# display_spi.net
KiCad netlist of a schematic drawn in EAGLE
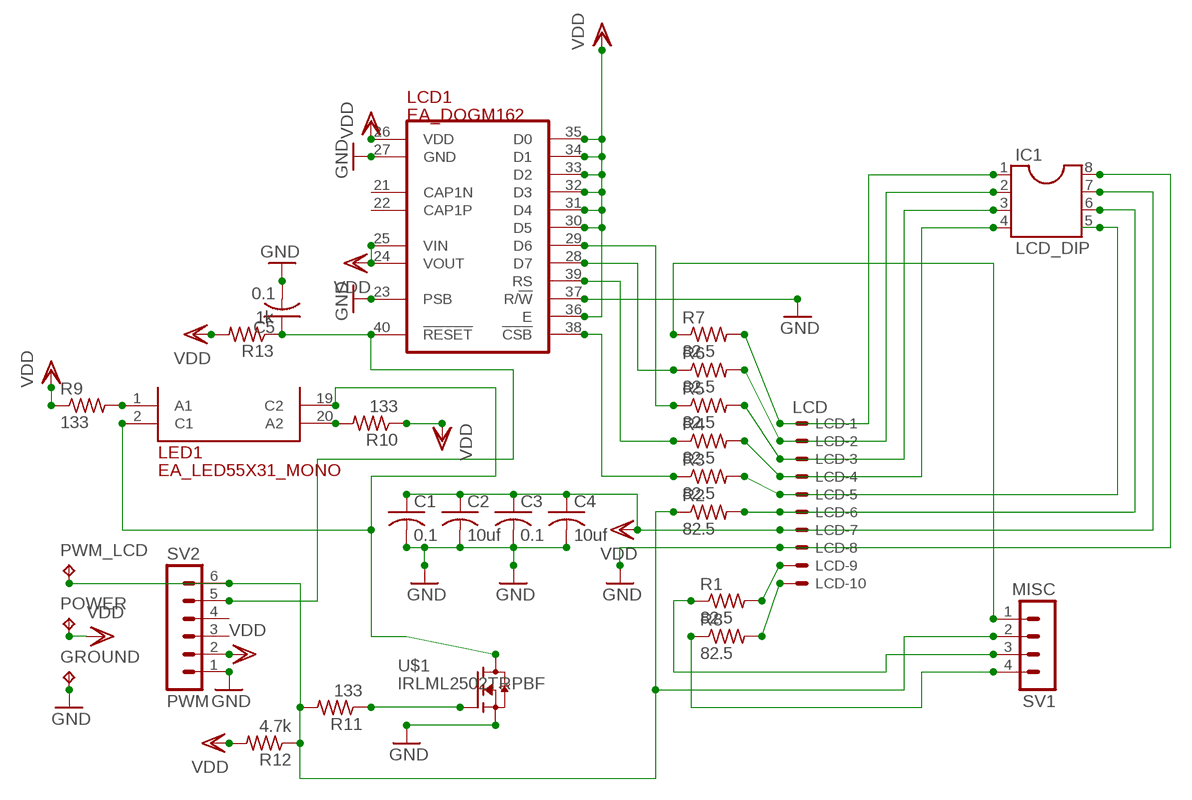
[diagram p0: schematic, sheet 1]

(export (version "E")
  (design (tool "Eeschema 10.0.6"))
  (components
    (comp (ref "C1")
      (value "0.1")
      (footprint "eagle-import:C1206")
      (libsource (lib "eagle-import") (part "C-USC1206"))
    )
    (comp (ref "C2")
      (value "10uf")
      (footprint "eagle-import:C1206")
      (libsource (lib "eagle-import") (part "C-USC1206"))
    )
    (comp (ref "C3")
      (value "0.1")
      (footprint "eagle-import:C1206")
      (libsource (lib "eagle-import") (part "C-USC1206"))
    )
    (comp (ref "C4")
      (value "10uf")
      (footprint "eagle-import:C1206")
      (libsource (lib "eagle-import") (part "C-USC1206"))
    )
    (comp (ref "C5")
      (value "0.1")
      (footprint "eagle-import:C1206")
      (libsource (lib "eagle-import") (part "C-USC1206"))
    )
    (comp (ref "GROUND")
      (value "TPB1,27")
      (footprint "eagle-import:B1,27")
      (libsource (lib "eagle-import") (part "TPB1,27"))
    )
    (comp (ref "IC1")
      (value "LCD_DIP")
      (footprint "eagle-import:SOCKET-08")
      (libsource (lib "eagle-import") (part "DIL8S"))
    )
    (comp (ref "LCD")
      (value "LCD")
      (footprint "eagle-import:22-23-2101")
      (fields (field (name "MF") "MOLEX") (field (name "MPN") "22-23-2101"))
      (libsource (lib "eagle-import") (part "22-23-2101"))
    )
    (comp (ref "LCD1")
      (value "EA_DOGM162")
      (footprint "eagle-import:EA_DOGM")
      (libsource (lib "eagle-import") (part "EA_DOGM162"))
    )
    (comp (ref "LED1")
      (value "EA_LED55X31_MONO")
      (footprint "eagle-import:EA_LED55X31")
      (libsource (lib "eagle-import") (part "EA_LED55X31_MONO"))
    )
    (comp (ref "POWER")
      (value "TPB1,27")
      (footprint "eagle-import:B1,27")
      (libsource (lib "eagle-import") (part "TPB1,27"))
    )
    (comp (ref "PWM_LCD")
      (value "PWM")
      (footprint "eagle-import:B1,27")
      (libsource (lib "eagle-import") (part "TPB1,27"))
    )
    (comp (ref "R1")
      (value "82.5")
      (footprint "eagle-import:R0805")
      (libsource (lib "eagle-import") (part "R-US_R0805"))
    )
    (comp (ref "R2")
      (value "82.5")
      (footprint "eagle-import:R0805")
      (libsource (lib "eagle-import") (part "R-US_R0805"))
    )
    (comp (ref "R3")
      (value "82.5")
      (footprint "eagle-import:R0805")
      (libsource (lib "eagle-import") (part "R-US_R0805"))
    )
    (comp (ref "R4")
      (value "82.5")
      (footprint "eagle-import:R0805")
      (libsource (lib "eagle-import") (part "R-US_R0805"))
    )
    (comp (ref "R5")
      (value "82.5")
      (footprint "eagle-import:R0805")
      (libsource (lib "eagle-import") (part "R-US_R0805"))
    )
    (comp (ref "R6")
      (value "82.5")
      (footprint "eagle-import:R0805")
      (libsource (lib "eagle-import") (part "R-US_R0805"))
    )
    (comp (ref "R7")
      (value "82.5")
      (footprint "eagle-import:R0805")
      (libsource (lib "eagle-import") (part "R-US_R0805"))
    )
    (comp (ref "R8")
      (value "82.5")
      (footprint "eagle-import:R0805")
      (libsource (lib "eagle-import") (part "R-US_R0805"))
    )
    (comp (ref "R9")
      (value "133")
      (footprint "eagle-import:R1206")
      (libsource (lib "eagle-import") (part "R-US_R1206"))
    )
    (comp (ref "R10")
      (value "133")
      (footprint "eagle-import:R1206")
      (libsource (lib "eagle-import") (part "R-US_R1206"))
    )
    (comp (ref "R11")
      (value "133")
      (footprint "eagle-import:R1206")
      (libsource (lib "eagle-import") (part "R-US_R1206"))
    )
    (comp (ref "R12")
      (value "4.7k")
      (footprint "eagle-import:R1206")
      (libsource (lib "eagle-import") (part "R-US_R1206"))
    )
    (comp (ref "R13")
      (value "1k")
      (footprint "eagle-import:R1206")
      (libsource (lib "eagle-import") (part "R-US_R1206"))
    )
    (comp (ref "SV1")
      (value "MISC")
      (footprint "eagle-import:MA04-1")
      (libsource (lib "eagle-import") (part "MA04-1"))
    )
    (comp (ref "SV2")
      (value "PWM")
      (footprint "eagle-import:MA06-1")
      (libsource (lib "eagle-import") (part "MA06-1"))
    )
    (comp (ref "U$1")
      (value "IRLML2502TRPBF")
      (footprint "eagle-import:SOT23")
      (fields (field (name "DIGI-KEY_PART_NUMBER") "IRLML2502TRPBFCT-ND") (field (name "MF") "Infineon"))
      (libsource (lib "eagle-import") (part "IRLML2502TRPBF"))
    )
  )
  (nets
    (net (code "1") (name "GND") (class "Default")
      (node (ref "C1") (pin "2") (pinfunction "2_2") (pintype "passive"))
      (node (ref "C2") (pin "2") (pinfunction "2_2") (pintype "passive"))
      (node (ref "C3") (pin "2") (pinfunction "2_2") (pintype "passive"))
      (node (ref "C4") (pin "2") (pinfunction "2_2") (pintype "passive"))
      (node (ref "C5") (pin "2") (pinfunction "2_2") (pintype "passive"))
      (node (ref "GROUND") (pin "TP") (pinfunction "TP_TP") (pintype "input"))
      (node (ref "IC1") (pin "8") (pinfunction "8_8") (pintype "passive"))
      (node (ref "LCD") (pin "8") (pinfunction "S_8") (pintype "passive"))
      (node (ref "LCD1") (pin "23") (pinfunction "PSB_23") (pintype "input"))
      (node (ref "LCD1") (pin "27") (pinfunction "GND_27") (pintype "power_in"))
      (node (ref "LCD1") (pin "37") (pinfunction "R/~{W}_37") (pintype "input"))
      (node (ref "SV2") (pin "1") (pinfunction "1_1") (pintype "passive"))
      (node (ref "U$1") (pin "2") (pinfunction "S_2") (pintype "passive"))
    )
    (net (code "2") (name "Net-(LCD1-D6)") (class "Default")
      (node (ref "LCD1") (pin "29") (pinfunction "D6_29") (pintype "bidirectional"))
      (node (ref "R5") (pin "1") (pinfunction "1_1") (pintype "passive"))
    )
    (net (code "3") (name "Net-(LCD1-D7)") (class "Default")
      (node (ref "LCD1") (pin "28") (pinfunction "D7_28") (pintype "bidirectional"))
      (node (ref "R6") (pin "1") (pinfunction "1_1") (pintype "passive"))
    )
    (net (code "4") (name "Net-(LCD1-RS)") (class "Default")
      (node (ref "LCD1") (pin "39") (pinfunction "RS_39") (pintype "input"))
      (node (ref "R4") (pin "1") (pinfunction "1_1") (pintype "passive"))
    )
    (net (code "5") (name "Net-(LCD1-~{CSB})") (class "Default")
      (node (ref "LCD1") (pin "38") (pinfunction "~{CSB}_38") (pintype "input"))
      (node (ref "R3") (pin "1") (pinfunction "1_1") (pintype "passive"))
    )
    (net (code "6") (name "Net-(LCD1-~{RESET})") (class "Default")
      (node (ref "C5") (pin "1") (pinfunction "1_1") (pintype "passive"))
      (node (ref "LCD1") (pin "40") (pinfunction "~{RESET}_40") (pintype "input"))
      (node (ref "R13") (pin "1") (pinfunction "1_1") (pintype "passive"))
      (node (ref "SV2") (pin "5") (pinfunction "5_5") (pintype "passive"))
    )
    (net (code "7") (name "Net-(LCDA-S)") (class "Default")
      (node (ref "IC1") (pin "1") (pinfunction "1_1") (pintype "passive"))
      (node (ref "LCD") (pin "1") (pinfunction "S_1") (pintype "passive"))
      (node (ref "R7") (pin "2") (pinfunction "2_2") (pintype "passive"))
    )
    (net (code "8") (name "Net-(LCDB-S)") (class "Default")
      (node (ref "LCD") (pin "10") (pinfunction "S_10") (pintype "passive"))
      (node (ref "R8") (pin "2") (pinfunction "2_2") (pintype "passive"))
    )
    (net (code "9") (name "Net-(LCDC-S)") (class "Default")
      (node (ref "IC1") (pin "2") (pinfunction "2_2") (pintype "passive"))
      (node (ref "LCD") (pin "2") (pinfunction "S_2") (pintype "passive"))
      (node (ref "R6") (pin "2") (pinfunction "2_2") (pintype "passive"))
    )
    (net (code "10") (name "Net-(LCDD-S)") (class "Default")
      (node (ref "IC1") (pin "3") (pinfunction "3_3") (pintype "passive"))
      (node (ref "LCD") (pin "3") (pinfunction "S_3") (pintype "passive"))
      (node (ref "R5") (pin "2") (pinfunction "2_2") (pintype "passive"))
    )
    (net (code "11") (name "Net-(LCDE-S)") (class "Default")
      (node (ref "IC1") (pin "4") (pinfunction "4_4") (pintype "passive"))
      (node (ref "LCD") (pin "4") (pinfunction "S_4") (pintype "passive"))
      (node (ref "R4") (pin "2") (pinfunction "2_2") (pintype "passive"))
    )
    (net (code "12") (name "Net-(LCDF-S)") (class "Default")
      (node (ref "IC1") (pin "5") (pinfunction "5_5") (pintype "passive"))
      (node (ref "LCD") (pin "5") (pinfunction "S_5") (pintype "passive"))
      (node (ref "R3") (pin "2") (pinfunction "2_2") (pintype "passive"))
    )
    (net (code "13") (name "Net-(LCDG-S)") (class "Default")
      (node (ref "IC1") (pin "6") (pinfunction "6_6") (pintype "passive"))
      (node (ref "LCD") (pin "6") (pinfunction "S_6") (pintype "passive"))
      (node (ref "R2") (pin "2") (pinfunction "2_2") (pintype "passive"))
    )
    (net (code "14") (name "Net-(LCDJ-S)") (class "Default")
      (node (ref "LCD") (pin "9") (pinfunction "S_9") (pintype "passive"))
      (node (ref "R1") (pin "2") (pinfunction "2_2") (pintype "passive"))
    )
    (net (code "15") (name "Net-(LED1-A1)") (class "Default")
      (node (ref "LED1") (pin "1") (pinfunction "A1_1") (pintype "passive"))
      (node (ref "R9") (pin "2") (pinfunction "2_2") (pintype "passive"))
    )
    (net (code "16") (name "Net-(LED1-A2)") (class "Default")
      (node (ref "LED1") (pin "20") (pinfunction "A2_20") (pintype "passive"))
      (node (ref "R10") (pin "2") (pinfunction "2_2") (pintype "passive"))
    )
    (net (code "17") (name "Net-(LED1-C1)") (class "Default")
      (node (ref "LED1") (pin "19") (pinfunction "C2_19") (pintype "passive"))
      (node (ref "LED1") (pin "2") (pinfunction "C1_2") (pintype "passive"))
      (node (ref "U$1") (pin "3") (pinfunction "D_3") (pintype "passive"))
    )
    (net (code "18") (name "Net-(PWM_LCD-PadTP)") (class "Default")
      (node (ref "PWM_LCD") (pin "TP") (pinfunction "TP_TP") (pintype "input"))
      (node (ref "R11") (pin "2") (pinfunction "2_2") (pintype "passive"))
      (node (ref "R12") (pin "1") (pinfunction "1_1") (pintype "passive"))
      (node (ref "R2") (pin "1") (pinfunction "1_1") (pintype "passive"))
      (node (ref "SV1") (pin "2") (pinfunction "2_2") (pintype "passive"))
      (node (ref "SV2") (pin "6") (pinfunction "6_6") (pintype "passive"))
    )
    (net (code "19") (name "Net-(R1-Pad1)") (class "Default")
      (node (ref "R1") (pin "1") (pinfunction "1_1") (pintype "passive"))
      (node (ref "SV1") (pin "3") (pinfunction "3_3") (pintype "passive"))
    )
    (net (code "20") (name "Net-(R7-Pad1)") (class "Default")
      (node (ref "R7") (pin "1") (pinfunction "1_1") (pintype "passive"))
      (node (ref "SV1") (pin "1") (pinfunction "1_1") (pintype "passive"))
    )
    (net (code "21") (name "Net-(R8-Pad1)") (class "Default")
      (node (ref "R8") (pin "1") (pinfunction "1_1") (pintype "passive"))
      (node (ref "SV1") (pin "4") (pinfunction "4_4") (pintype "passive"))
    )
    (net (code "22") (name "Net-(U$1-G)") (class "Default")
      (node (ref "R11") (pin "1") (pinfunction "1_1") (pintype "passive"))
      (node (ref "U$1") (pin "1") (pinfunction "G_1") (pintype "passive"))
    )
    (net (code "23") (name "VDD") (class "Default")
      (node (ref "C1") (pin "1") (pinfunction "1_1") (pintype "passive"))
      (node (ref "C2") (pin "1") (pinfunction "1_1") (pintype "passive"))
      (node (ref "C3") (pin "1") (pinfunction "1_1") (pintype "passive"))
      (node (ref "C4") (pin "1") (pinfunction "1_1") (pintype "passive"))
      (node (ref "IC1") (pin "7") (pinfunction "7_7") (pintype "passive"))
      (node (ref "LCD") (pin "7") (pinfunction "S_7") (pintype "passive"))
      (node (ref "LCD1") (pin "24") (pinfunction "VOUT_24") (pintype "passive"))
      (node (ref "LCD1") (pin "25") (pinfunction "VIN_25") (pintype "passive"))
      (node (ref "LCD1") (pin "26") (pinfunction "VDD_26") (pintype "power_in"))
      (node (ref "LCD1") (pin "30") (pinfunction "D5_30") (pintype "bidirectional"))
      (node (ref "LCD1") (pin "31") (pinfunction "D4_31") (pintype "bidirectional"))
      (node (ref "LCD1") (pin "32") (pinfunction "D3_32") (pintype "bidirectional"))
      (node (ref "LCD1") (pin "33") (pinfunction "D2_33") (pintype "bidirectional"))
      (node (ref "LCD1") (pin "34") (pinfunction "D1_34") (pintype "bidirectional"))
      (node (ref "LCD1") (pin "35") (pinfunction "D0_35") (pintype "bidirectional"))
      (node (ref "LCD1") (pin "36") (pinfunction "E_36") (pintype "input"))
      (node (ref "POWER") (pin "TP") (pinfunction "TP_TP") (pintype "input"))
      (node (ref "R10") (pin "1") (pinfunction "1_1") (pintype "passive"))
      (node (ref "R12") (pin "2") (pinfunction "2_2") (pintype "passive"))
      (node (ref "R13") (pin "2") (pinfunction "2_2") (pintype "passive"))
      (node (ref "R9") (pin "1") (pinfunction "1_1") (pintype "passive"))
      (node (ref "SV2") (pin "2") (pinfunction "2_2") (pintype "passive"))
    )
    (net (code "24") (name "unconnected-(LCD1-CAP1N-Pad21)") (class "Default")
      (node (ref "LCD1") (pin "21") (pinfunction "CAP1N_21") (pintype "passive"))
    )
    (net (code "25") (name "unconnected-(LCD1-CAP1P-Pad22)") (class "Default")
      (node (ref "LCD1") (pin "22") (pinfunction "CAP1P_22") (pintype "passive"))
    )
    (net (code "26") (name "unconnected-(SV2-Pad3)") (class "Default")
      (node (ref "SV2") (pin "3") (pinfunction "3_3") (pintype "passive"))
    )
    (net (code "27") (name "unconnected-(SV2-Pad4)") (class "Default")
      (node (ref "SV2") (pin "4") (pinfunction "4_4") (pintype "passive"))
    )
  )
)
